# CM5_Schem_V2.net
KiCad netlist of a schematic drawn in Altium Designer
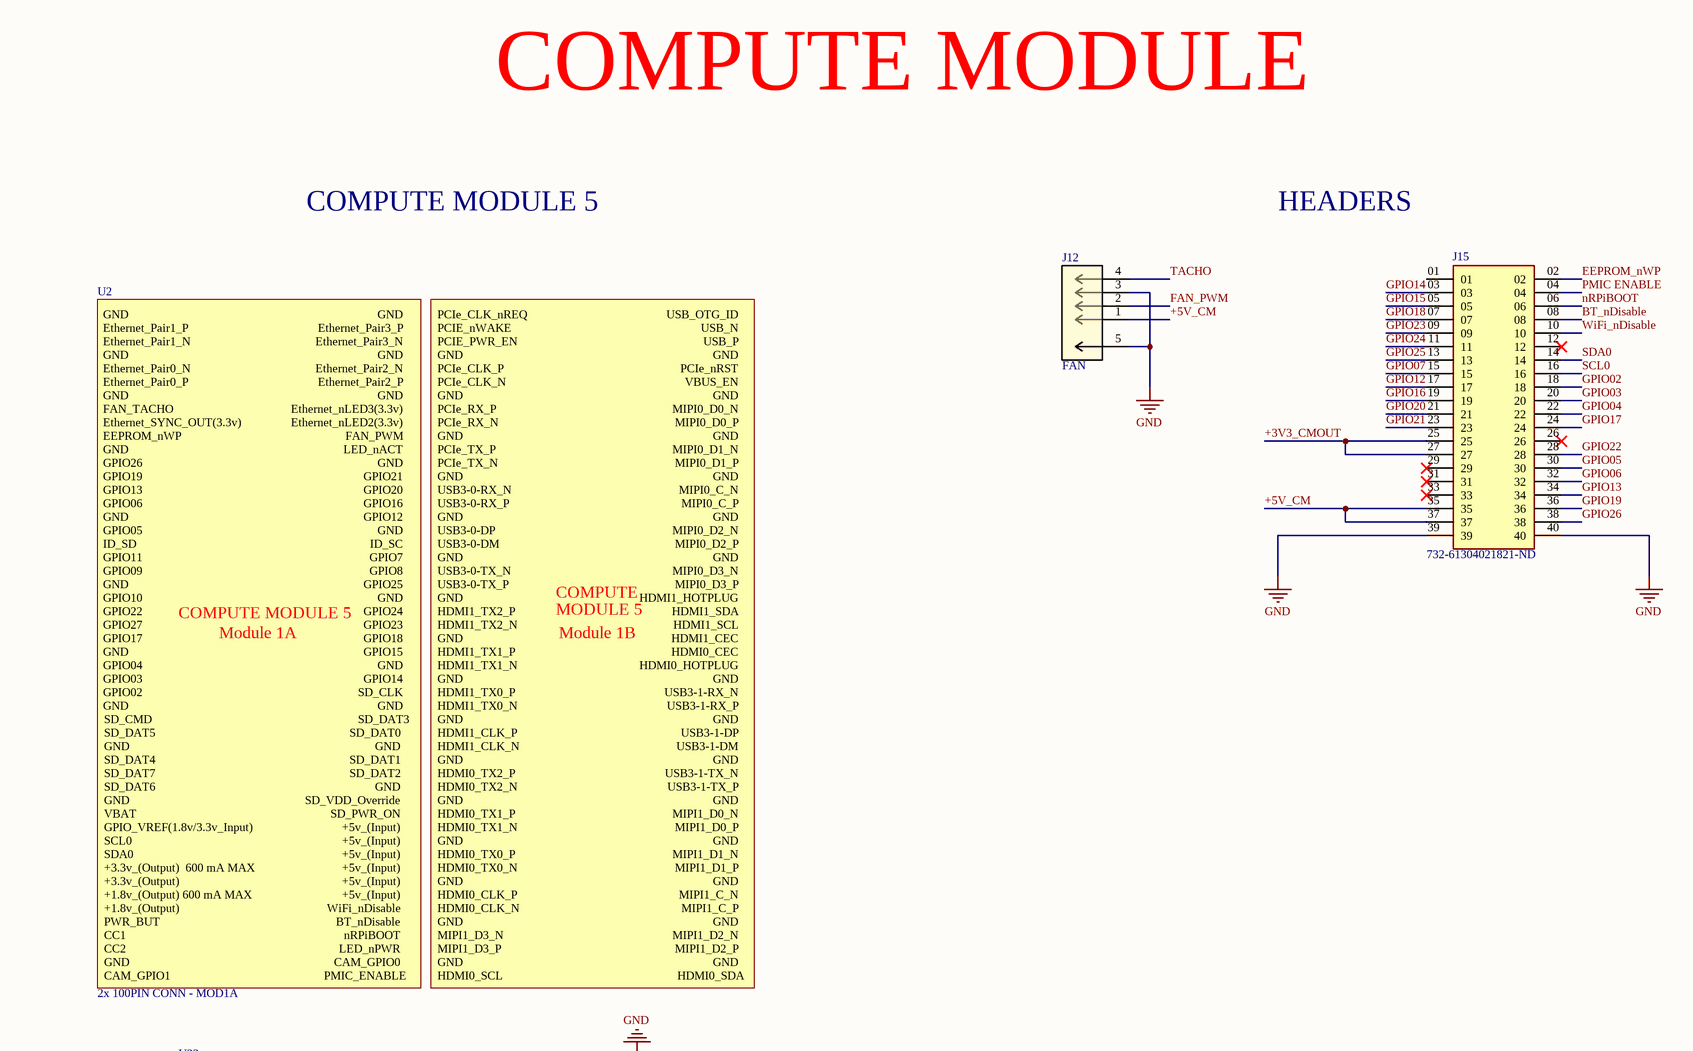
[diagram p0: CM5_Schem_V2.SchDoc, top left]
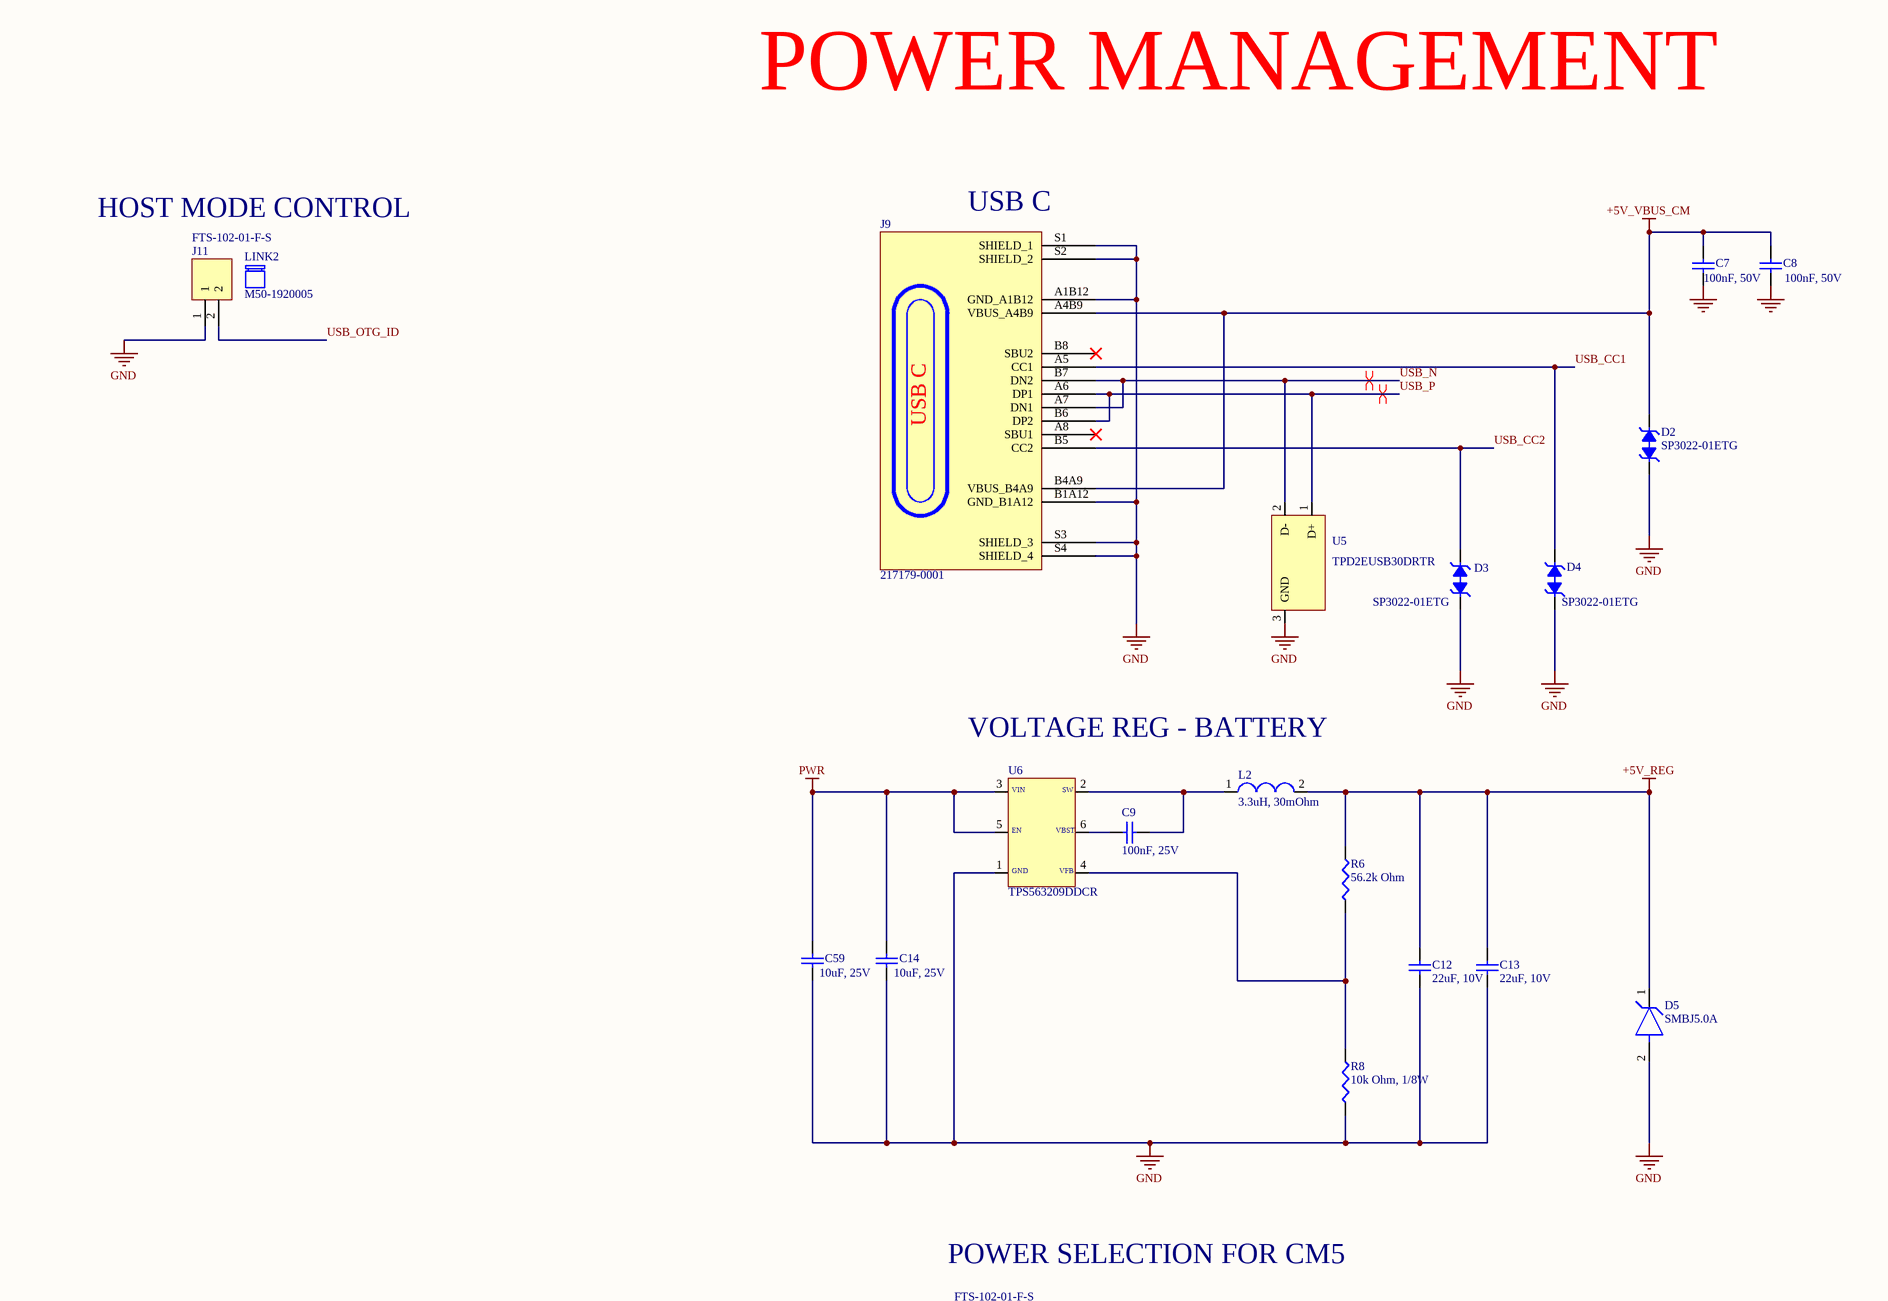
[diagram p1: CM5_Schem_V2.SchDoc, top right]
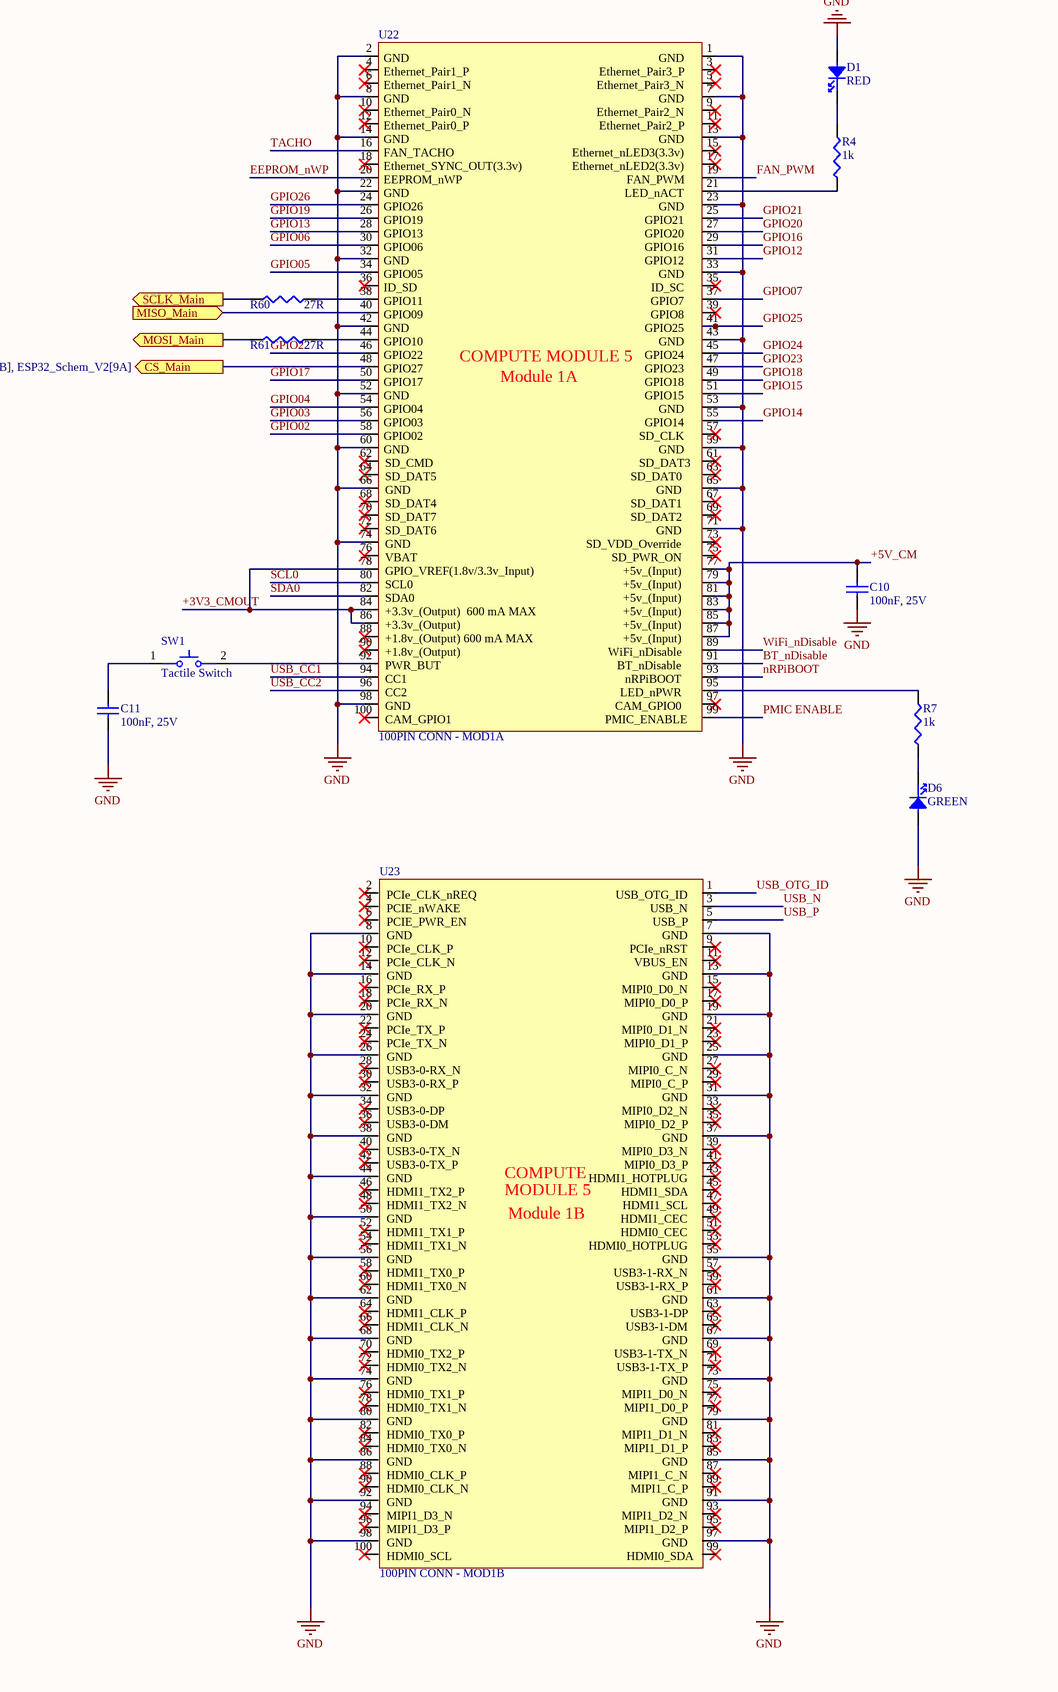
[diagram p2: CM5_Schem_V2.SchDoc, bottom left]
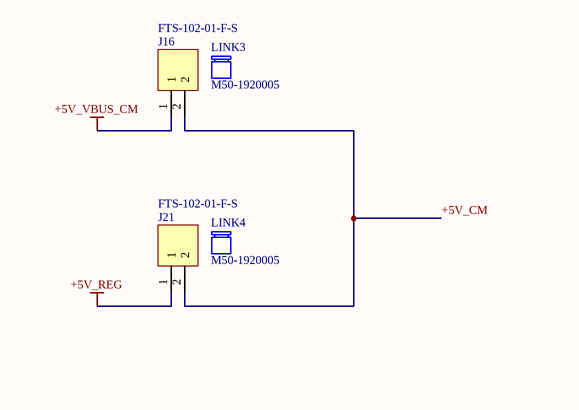
[diagram p3: CM5_Schem_V2.SchDoc, bottom right]

(export (version "E")
  (design (tool "Eeschema 10.0.6"))
  (components
    (comp (ref "C7")
      (value "100nF, 50V")
      (footprint "CAPC1005X55N")
      (fields
        (field (name "MANUFACTURER") "Samsung")
        (field (name "MANUFACTURER PART NUMBER") "CL05B104KB54PNC")
        (field (name "LCSC PART NUMBER") "C307331")
      )
      (libsource (lib "Schlib") (part "CL05B104KB54PNC"))
    )
    (comp (ref "C8")
      (value "100nF, 50V")
      (footprint "CAPC1005X55N")
      (fields
        (field (name "MANUFACTURER") "Samsung")
        (field (name "MANUFACTURER PART NUMBER") "CL05B104KB54PNC")
        (field (name "LCSC PART NUMBER") "C307331")
      )
      (libsource (lib "Schlib") (part "CL05B104KB54PNC"))
    )
    (comp (ref "C9")
      (value "100nF, 25V")
      (footprint "CAP_X7R_0805_AVX-M")
      (description "25V 100Nf X7R 10% 0805 Multilayer Ceramic Capacitors Mlcc Smd/Smt Rohs")
      (fields
        (field (name "MANUFACTURER") "Yageo Group")
        (field (name "MANUFACTURER PART NUMBER") "CC0805KRX7R8BB104")
      )
      (libsource (lib "Schlib_CM5+ESP32") (part "CC0805KRX7R8BB104"))
    )
    (comp (ref "C10")
      (value "100nF, 25V")
      (footprint "CAP_X7R_0805_AVX-M")
      (description "25V 100Nf X7R 10% 0805 Multilayer Ceramic Capacitors Mlcc Smd/Smt Rohs")
      (fields
        (field (name "MANUFACTURER") "Yageo Group")
        (field (name "MANUFACTURER PART NUMBER") "CC0805KRX7R8BB104")
      )
      (libsource (lib "Schlib_CM5+ESP32") (part "CC0805KRX7R8BB104"))
    )
    (comp (ref "C11")
      (value "100nF, 25V")
      (footprint "CAP_X7R_0805_AVX-M")
      (description "25V 100Nf X7R 10% 0805 Multilayer Ceramic Capacitors Mlcc Smd/Smt Rohs")
      (fields
        (field (name "MANUFACTURER") "Yageo Group")
        (field (name "MANUFACTURER PART NUMBER") "CC0805KRX7R8BB104")
      )
      (libsource (lib "Schlib_CM5+ESP32") (part "CC0805KRX7R8BB104"))
    )
    (comp (ref "C12")
      (value "22uF, 10V")
      (footprint "CAP_1608_TDK-M")
      (description "CAP CER 22UF 10V X5R 0603")
      (fields
        (field (name "MANUFACTURER") "TDK")
        (field (name "MANUFACTURER PART NUMBER") "C1608X5R1A226M080AC")
      )
      (libsource (lib "Schlib_CM5+ESP32") (part "C1608X5R1A226M080AC"))
    )
    (comp (ref "C13")
      (value "22uF, 10V")
      (footprint "CAP_1608_TDK-M")
      (description "CAP CER 22UF 10V X5R 0603")
      (fields
        (field (name "MANUFACTURER") "TDK")
        (field (name "MANUFACTURER PART NUMBER") "C1608X5R1A226M080AC")
      )
      (libsource (lib "Schlib_CM5+ESP32") (part "C1608X5R1A226M080AC"))
    )
    (comp (ref "C14")
      (value "10uF, 25V")
      (footprint "CAPC2012X95N")
      (description "CAP CER 10UF 25V X5R 0805")
      (fields
        (field (name "MANUFACTURER") "TAIYO YUDEN")
        (field (name "MANUFACTURER PART NUMBER") "TMK212BBJ106KG-T")
      )
      (libsource (lib "Schlib_CM5+ESP32") (part "TMK212BBJ106KG-T"))
    )
    (comp (ref "C59")
      (value "10uF, 25V")
      (footprint "CAPC2012X95N")
      (description "CAP CER 10UF 25V X5R 0805")
      (fields
        (field (name "MANUFACTURER") "TAIYO YUDEN")
        (field (name "MANUFACTURER PART NUMBER") "TMK212BBJ106KG-T")
      )
      (libsource (lib "Schlib_CM5+ESP32") (part "TMK212BBJ106KG-T"))
    )
    (comp (ref "D1")
      (value "RED")
      (footprint "LED0402R")
      (description "Single Color LED, Super Red, 0.5mm")
      (fields
        (field (name "MANUFACTURER") "Vishay")
        (field (name "MANUFACTURER PART NUMBER") "VLMS1500-GS08")
      )
      (libsource (lib "Schlib_PersonalProject") (part "VLMS1500-GS08"))
    )
    (comp (ref "D2")
      (value "SP3022-01ETG")
      (footprint "SOD882")
      (description "TVS DIODE 5.3VWM 12VC SOD882")
      (fields (field (name "MANUFACTURER") "Littelfuse") (field (name "LCSC PART NUMBER") "C126840"))
      (libsource (lib "Schlib_CM5+ESP32") (part "SP3022-01ETG"))
    )
    (comp (ref "D3")
      (value "SP3022-01ETG")
      (footprint "SOD882")
      (description "TVS DIODE 5.3VWM 12VC SOD882")
      (fields (field (name "MANUFACTURER") "Littelfuse") (field (name "LCSC PART NUMBER") "C126840"))
      (libsource (lib "Schlib_CM5+ESP32") (part "SP3022-01ETG"))
    )
    (comp (ref "D4")
      (value "SP3022-01ETG")
      (footprint "SOD882")
      (description "TVS DIODE 5.3VWM 12VC SOD882")
      (fields (field (name "MANUFACTURER") "Littelfuse") (field (name "LCSC PART NUMBER") "C126840"))
      (libsource (lib "Schlib_CM5+ESP32") (part "SP3022-01ETG"))
    )
    (comp (ref "D5")
      (value "SMBJ5.0A")
      (footprint "DO-214AASMB_J-BEND_LTF-M")
      (description "TVS DIODE 5VWM 9.2VC DO214AA")
      (fields (field (name "MANUFACTURER") "Littelfuse") (field (name "LCSC PART NUMBER") "C83333"))
      (libsource (lib "Schlib_CM5+ESP32") (part "SMBJ5.0A"))
    )
    (comp (ref "D6")
      (value "GREEN")
      (footprint "LED0402G")
      (description "Single Color LED, Yellow Green, 0.5mm")
      (fields
        (field (name "MANUFACTURER") "Vishay")
        (field (name "MANUFACTURER PART NUMBER") "VLMG1500-GS08")
      )
      (libsource (lib "Schlib_PersonalProject") (part "VLMG1500-GS08"))
    )
    (comp (ref "J9")
      (value "217179-0001")
      (footprint "FP-2171790001-MFG")
      (description "USB Connector, 16 Contact(s), Female, Right Angle, Surface Mount Terminal, Locking, Receptacle")
      (fields (field (name "MANUFACTURER") "Molex") (field (name "LCSC PART NUMBER") "C3197684"))
      (libsource (lib "Schlib_PersonalProject") (part "217179-0001"))
    )
    (comp (ref "J11")
      (value "FTS-102-01-F-S")
      (footprint "HDR_1x2_1.27MM")
      (description "Board Connector, 2 Contact(s), 1 Row(s), Male, Straight, Solder Terminal")
      (fields (field (name "MANUFACTURER") "Samtec") (field (name "LCSC PART NUMBER") "C6045317"))
      (libsource (lib "Schlib_PersonalProject") (part "FTS-102-01-F-S"))
    )
    (comp (ref "J12")
      (value "FAN")
      (footprint "CONN4_BM04B-SRSS_JST")
      (description "CONN HEADER SMD 4POS 1MM")
      (fields (field (name "MANUFACTURER") "JST") (field (name "MANUFACTURER PART NUMBER") "BM04B-SRSS-TB"))
      (libsource (lib "Schlib_CM5+ESP32") (part "BM04B-SRSS-TB"))
    )
    (comp (ref "J15")
      (value "732-61304021821-ND")
      (footprint "SAMTEC_MTSW-120-X-X-D-X")
      (description "Pin Header, Board-to-Board, 2.54 mm, 2 Rows, 40 Contacts, Through Hole, MTSW Series")
      (fields
        (field (name "MANUFACTURER") "Samtec")
        (field (name "MANUFACTURER PART NUMBER") "MTSW-120-22-T-D-380")
      )
      (libsource (lib "Schlib_CM5+ESP32") (part "MTSW-120-22-T-D-380"))
    )
    (comp (ref "J16")
      (value "FTS-102-01-F-S")
      (footprint "HDR_1x2_1.27MM")
      (description "Board Connector, 2 Contact(s), 1 Row(s), Male, Straight, Solder Terminal")
      (fields (field (name "MANUFACTURER") "Samtec") (field (name "LCSC PART NUMBER") "C6045317"))
      (libsource (lib "Schlib_PersonalProject") (part "FTS-102-01-F-S"))
    )
    (comp (ref "J21")
      (value "FTS-102-01-F-S")
      (footprint "HDR_1x2_1.27MM")
      (description "Board Connector, 2 Contact(s), 1 Row(s), Male, Straight, Solder Terminal")
      (fields (field (name "MANUFACTURER") "Samtec") (field (name "LCSC PART NUMBER") "C6045317"))
      (libsource (lib "Schlib_PersonalProject") (part "FTS-102-01-F-S"))
    )
    (comp (ref "L2")
      (value "3.3uH, 30mOhm")
      (footprint "IND_VLS6045EX-3R3N")
      (description "FIXED IND 3.3UH 4.95A 30MOHM SMD")
      (fields (field (name "MANUFACTURER") "TDK") (field (name "MANUFACTURER PART NUMBER") "VLS6045EX-3R3N"))
      (libsource (lib "Schlib_CM5+ESP32") (part "VLS6045EX-3R3N"))
    )
    (comp (ref "LINK2")
      (value "M50-1920005")
      (description "Interconnection Device")
      (fields (field (name "MANUFACTURER") "Harwin") (field (name "LCSC PART NUMBER") "C6985646"))
      (libsource (lib "Schlib_PersonalProject") (part "M50-1920005"))
    )
    (comp (ref "LINK3")
      (value "M50-1920005")
      (description "Interconnection Device")
      (fields (field (name "MANUFACTURER") "Harwin") (field (name "LCSC PART NUMBER") "C6985646"))
      (libsource (lib "Schlib_PersonalProject") (part "M50-1920005"))
    )
    (comp (ref "LINK4")
      (value "M50-1920005")
      (description "Interconnection Device")
      (fields (field (name "MANUFACTURER") "Harwin") (field (name "LCSC PART NUMBER") "C6985646"))
      (libsource (lib "Schlib_PersonalProject") (part "M50-1920005"))
    )
    (comp (ref "R4")
      (value "1k")
      (footprint "RESC1005X40N")
      (description "RES 1K OHM 1% 1/16W 0402")
      (fields
        (field (name "MANUFACTURER") "Yageo")
        (field (name "MANUFACTURER PART NUMBER") "RC0402FR-071KL")
      )
      (libsource (lib "Schlib_CM5+ESP32") (part "RC0402FR-071KL"))
    )
    (comp (ref "R6")
      (value "56.2k Ohm")
      (footprint "RESC0603X26N")
      (description "RES 56.2K OHM 1% 1/20W 0201")
      (fields
        (field (name "MANUFACTURER") "Yageo")
        (field (name "MANUFACTURER PART NUMBER") "RC0201FR-0756K2L")
      )
      (libsource (lib "Schlib_CM5+ESP32") (part "RC0201FR-0756K2L"))
    )
    (comp (ref "R7")
      (value "1k")
      (footprint "RESC1005X40N")
      (description "RES 1K OHM 1% 1/16W 0402")
      (fields
        (field (name "MANUFACTURER") "Yageo")
        (field (name "MANUFACTURER PART NUMBER") "RC0402FR-071KL")
      )
      (libsource (lib "Schlib_CM5+ESP32") (part "RC0402FR-071KL"))
    )
    (comp (ref "R8")
      (value "10k Ohm, 1/8W")
      (footprint "RESC1005X40N")
      (description "RES 10K OHM 1% 1/8W 0402")
      (fields
        (field (name "MANUFACTURER") "Yageo Group")
        (field (name "MANUFACTURER PART NUMBER") "RC0402FR-7W10KL")
      )
      (libsource (lib "Schlib_CM5+ESP32") (part "RC0402FR-7W10KL"))
    )
    (comp (ref "R60")
      (value "27R")
      (footprint "RESC1005X37N")
      (fields
        (field (name "MANUFACTURER") "Yageo")
        (field (name "MANUFACTURER PART NUMBER") "RC0402FR-0727RL")
        (field (name "TOLERANCE") "1%")
      )
      (libsource (lib "Schlib") (part "RC0402FR-0727RL"))
    )
    (comp (ref "R61")
      (value "27R")
      (footprint "RESC1005X37N")
      (fields
        (field (name "MANUFACTURER") "Yageo")
        (field (name "MANUFACTURER PART NUMBER") "RC0402FR-0727RL")
        (field (name "TOLERANCE") "1%")
      )
      (libsource (lib "Schlib") (part "RC0402FR-0727RL"))
    )
    (comp (ref "SW1")
      (value "Tactile Switch")
      (footprint "SWITCH_43SMTR92LFS")
      (description "SWITCH TACTILE SPST-NO 0.05A 12V")
      (fields
        (field (name "MANUFACTURER") "ITT C&K")
        (field (name "MANUFACTURER PART NUMBER") "PTS645SM43SMTR92LFS")
      )
      (libsource (lib "Schlib_CM5+ESP32") (part "PTS645SM43SMTR92LFS"))
    )
    (comp (ref "U2")
      (value "2x 100PIN CONN - MOD1A")
      (footprint "RPI CM5")
      (description "2x CONN RCPT 100POS SMD GOLD")
      (fields
        (field (name "MANUFACTURER") "Hirose")
        (field (name "MANUFACTURER PART NUMBER") "DF40C-100DS-0.4V(51)")
      )
      (libsource (lib "Schlib_CM5+ESP32") (part "CM5 Courtyard"))
    )
    (comp (ref "U5")
      (value "TPD2EUSB30DRTR")
      (footprint "SOTFL35P100X50-3N")
      (description "TVS DIODE 5.5VWM 8VC SOT3")
      (fields (field (name "MANUFACTURER") "Texas Instruments") (field (name "LCSC PART NUMBER") "C97502"))
      (libsource (lib "Schlib_CM5+ESP32") (part "TPD2EUSB30DRTR"))
    )
    (comp (ref "U6")
      (value "TPS563209DDCR")
      (footprint "DDC0006A")
      (description "IC REG BUCK ADJ 3A SOT23")
      (fields (field (name "MANUFACTURER") "Texas Instruments") (field (name "LCSC PART NUMBER") "C181974"))
      (libsource (lib "Schlib_CM5+ESP32") (part "TPS563209DDCR"))
    )
    (comp (ref "U22")
      (value "100PIN CONN - MOD1A")
      (footprint "HIROSE_DF40C-100DS-0.4V(51)")
      (description "CONN RCPT 100POS SMD GOLD")
      (fields
        (field (name "MANUFACTURER") "Hirose")
        (field (name "MANUFACTURER PART NUMBER") "DF40C-100DS-0.4V(51)")
      )
      (libsource (lib "Schlib_CM5+ESP32") (part "DF40C-100DS-0.4V(51)_MOD1A"))
    )
    (comp (ref "U23")
      (value "100PIN CONN - MOD1B")
      (footprint "HIROSE_DF40C-100DS-0.4V(51)")
      (description "CONN RCPT 100POS SMD GOLD")
      (fields
        (field (name "MANUFACTURER") "Hirose")
        (field (name "MANUFACTURER PART NUMBER") "DF40C-100DS-0.4V(51)")
      )
      (libsource (lib "Schlib_CM5+ESP32") (part "DF40C-100DS-0.4V(51)_MOD1B"))
    )
  )
  (nets
    (net (code "1") (name "+5V_REG") (class "Default")
      (node (ref "C12") (pin "1") (pinfunction "1_1") (pintype "passive"))
      (node (ref "C13") (pin "1") (pinfunction "1_1") (pintype "passive"))
      (node (ref "D5") (pin "1") (pinfunction "1_1") (pintype "passive"))
      (node (ref "J21") (pin "1") (pinfunction "1_1") (pintype "passive"))
      (node (ref "L2") (pin "2") (pinfunction "2_2") (pintype "passive"))
      (node (ref "R6") (pin "2") (pinfunction "2_2") (pintype "passive"))
    )
    (net (code "2") (name "+5V_VBUS_CM") (class "Default")
      (node (ref "C7") (pin "2") (pinfunction "2_2") (pintype "passive"))
      (node (ref "C8") (pin "2") (pinfunction "2_2") (pintype "passive"))
      (node (ref "D2") (pin "2") (pinfunction "2_2") (pintype "passive"))
      (node (ref "J16") (pin "1") (pinfunction "1_1") (pintype "passive"))
      (node (ref "J9") (pin "A4B9") (pinfunction "VBUS_A4B9_A4B9") (pintype "passive"))
      (node (ref "J9") (pin "B4A9") (pinfunction "VBUS_B4A9_B4A9") (pintype "passive"))
    )
    (net (code "3") (name "/+3V3_CMOUT") (class "Default")
      (node (ref "J15") (pin "25") (pinfunction "25_25") (pintype "passive"))
      (node (ref "J15") (pin "27") (pinfunction "27_27") (pintype "passive"))
      (node (ref "U22") (pin "78") (pinfunction "78_78") (pintype "passive"))
      (node (ref "U22") (pin "84") (pinfunction "84_84") (pintype "passive"))
      (node (ref "U22") (pin "86") (pinfunction "86_86") (pintype "passive"))
    )
    (net (code "4") (name "/+5V_CM") (class "Default")
      (node (ref "C10") (pin "2") (pinfunction "2_2") (pintype "passive"))
      (node (ref "J12") (pin "1") (pinfunction "1_1") (pintype "passive"))
      (node (ref "J15") (pin "35") (pinfunction "35_35") (pintype "passive"))
      (node (ref "J15") (pin "37") (pinfunction "37_37") (pintype "passive"))
      (node (ref "J16") (pin "2") (pinfunction "2_2") (pintype "passive"))
      (node (ref "J21") (pin "2") (pinfunction "2_2") (pintype "passive"))
      (node (ref "U22") (pin "77") (pinfunction "77_77") (pintype "passive"))
      (node (ref "U22") (pin "79") (pinfunction "79_79") (pintype "passive"))
      (node (ref "U22") (pin "81") (pinfunction "81_81") (pintype "passive"))
      (node (ref "U22") (pin "83") (pinfunction "83_83") (pintype "passive"))
      (node (ref "U22") (pin "85") (pinfunction "85_85") (pintype "passive"))
      (node (ref "U22") (pin "87") (pinfunction "87_87") (pintype "passive"))
    )
    (net (code "5") (name "/BT_nDisable") (class "Default")
      (node (ref "J15") (pin "08") (pinfunction "08_08") (pintype "passive"))
      (node (ref "U22") (pin "91") (pinfunction "91_91") (pintype "passive"))
    )
    (net (code "6") (name "/CS_Main") (class "Default")
      (node (ref "U22") (pin "48") (pinfunction "48_48") (pintype "passive"))
    )
    (net (code "7") (name "/EEPROM_nWP") (class "Default")
      (node (ref "J15") (pin "02") (pinfunction "02_02") (pintype "passive"))
      (node (ref "U22") (pin "20") (pinfunction "20_20") (pintype "passive"))
    )
    (net (code "8") (name "/FAN_PWM") (class "Default")
      (node (ref "J12") (pin "2") (pinfunction "2_2") (pintype "passive"))
      (node (ref "U22") (pin "19") (pinfunction "19_19") (pintype "passive"))
    )
    (net (code "9") (name "/GPIO02") (class "Default")
      (node (ref "J15") (pin "18") (pinfunction "18_18") (pintype "passive"))
      (node (ref "U22") (pin "58") (pinfunction "58_58") (pintype "passive"))
    )
    (net (code "10") (name "/GPIO03") (class "Default")
      (node (ref "J15") (pin "20") (pinfunction "20_20") (pintype "passive"))
      (node (ref "U22") (pin "56") (pinfunction "56_56") (pintype "passive"))
    )
    (net (code "11") (name "/GPIO04") (class "Default")
      (node (ref "J15") (pin "22") (pinfunction "22_22") (pintype "passive"))
      (node (ref "U22") (pin "54") (pinfunction "54_54") (pintype "passive"))
    )
    (net (code "12") (name "/GPIO05") (class "Default")
      (node (ref "J15") (pin "30") (pinfunction "30_30") (pintype "passive"))
      (node (ref "U22") (pin "34") (pinfunction "34_34") (pintype "passive"))
    )
    (net (code "13") (name "/GPIO06") (class "Default")
      (node (ref "J15") (pin "32") (pinfunction "32_32") (pintype "passive"))
      (node (ref "U22") (pin "30") (pinfunction "30_30") (pintype "passive"))
    )
    (net (code "14") (name "/GPIO07") (class "Default")
      (node (ref "J15") (pin "15") (pinfunction "15_15") (pintype "passive"))
      (node (ref "U22") (pin "37") (pinfunction "37_37") (pintype "passive"))
    )
    (net (code "15") (name "/GPIO12") (class "Default")
      (node (ref "J15") (pin "17") (pinfunction "17_17") (pintype "passive"))
      (node (ref "U22") (pin "31") (pinfunction "31_31") (pintype "passive"))
    )
    (net (code "16") (name "/GPIO13") (class "Default")
      (node (ref "J15") (pin "34") (pinfunction "34_34") (pintype "passive"))
      (node (ref "U22") (pin "28") (pinfunction "28_28") (pintype "passive"))
    )
    (net (code "17") (name "/GPIO14") (class "Default")
      (node (ref "J15") (pin "03") (pinfunction "03_03") (pintype "passive"))
      (node (ref "U22") (pin "55") (pinfunction "55_55") (pintype "passive"))
    )
    (net (code "18") (name "/GPIO15") (class "Default")
      (node (ref "J15") (pin "05") (pinfunction "05_05") (pintype "passive"))
      (node (ref "U22") (pin "51") (pinfunction "51_51") (pintype "passive"))
    )
    (net (code "19") (name "/GPIO16") (class "Default")
      (node (ref "J15") (pin "19") (pinfunction "19_19") (pintype "passive"))
      (node (ref "U22") (pin "29") (pinfunction "29_29") (pintype "passive"))
    )
    (net (code "20") (name "/GPIO17") (class "Default")
      (node (ref "J15") (pin "24") (pinfunction "24_24") (pintype "passive"))
      (node (ref "U22") (pin "50") (pinfunction "50_50") (pintype "passive"))
    )
    (net (code "21") (name "/GPIO18") (class "Default")
      (node (ref "J15") (pin "07") (pinfunction "07_07") (pintype "passive"))
      (node (ref "U22") (pin "49") (pinfunction "49_49") (pintype "passive"))
    )
    (net (code "22") (name "/GPIO19") (class "Default")
      (node (ref "J15") (pin "36") (pinfunction "36_36") (pintype "passive"))
      (node (ref "U22") (pin "26") (pinfunction "26_26") (pintype "passive"))
    )
    (net (code "23") (name "/GPIO20") (class "Default")
      (node (ref "J15") (pin "21") (pinfunction "21_21") (pintype "passive"))
      (node (ref "U22") (pin "27") (pinfunction "27_27") (pintype "passive"))
    )
    (net (code "24") (name "/GPIO21") (class "Default")
      (node (ref "J15") (pin "23") (pinfunction "23_23") (pintype "passive"))
      (node (ref "U22") (pin "25") (pinfunction "25_25") (pintype "passive"))
    )
    (net (code "25") (name "/GPIO22") (class "Default")
      (node (ref "J15") (pin "28") (pinfunction "28_28") (pintype "passive"))
      (node (ref "U22") (pin "46") (pinfunction "46_46") (pintype "passive"))
    )
    (net (code "26") (name "/GPIO23") (class "Default")
      (node (ref "J15") (pin "09") (pinfunction "09_09") (pintype "passive"))
      (node (ref "U22") (pin "47") (pinfunction "47_47") (pintype "passive"))
    )
    (net (code "27") (name "/GPIO24") (class "Default")
      (node (ref "J15") (pin "11") (pinfunction "11_11") (pintype "passive"))
      (node (ref "U22") (pin "45") (pinfunction "45_45") (pintype "passive"))
    )
    (net (code "28") (name "/GPIO25") (class "Default")
      (node (ref "J15") (pin "13") (pinfunction "13_13") (pintype "passive"))
      (node (ref "U22") (pin "41") (pinfunction "41_41") (pintype "passive"))
    )
    (net (code "29") (name "/GPIO26") (class "Default")
      (node (ref "J15") (pin "38") (pinfunction "38_38") (pintype "passive"))
      (node (ref "U22") (pin "24") (pinfunction "24_24") (pintype "passive"))
    )
    (net (code "30") (name "/MISO_Main") (class "Default")
      (node (ref "U22") (pin "40") (pinfunction "40_40") (pintype "passive"))
    )
    (net (code "31") (name "/MOSI_Main") (class "Default")
      (node (ref "R61") (pin "1") (pinfunction "1_1") (pintype "passive"))
    )
    (net (code "32") (name "/PMIC ENABLE") (class "Default")
      (node (ref "J15") (pin "04") (pinfunction "04_04") (pintype "passive"))
      (node (ref "U22") (pin "99") (pinfunction "99_99") (pintype "passive"))
    )
    (net (code "33") (name "/SCL0") (class "Default")
      (node (ref "J15") (pin "16") (pinfunction "16_16") (pintype "passive"))
      (node (ref "U22") (pin "80") (pinfunction "80_80") (pintype "passive"))
    )
    (net (code "34") (name "/SCLK_Main") (class "Default")
      (node (ref "R60") (pin "1") (pinfunction "1_1") (pintype "passive"))
    )
    (net (code "35") (name "/SDA0") (class "Default")
      (node (ref "J15") (pin "14") (pinfunction "14_14") (pintype "passive"))
      (node (ref "U22") (pin "82") (pinfunction "82_82") (pintype "passive"))
    )
    (net (code "36") (name "/TACHO") (class "Default")
      (node (ref "J12") (pin "4") (pinfunction "4_4") (pintype "passive"))
      (node (ref "U22") (pin "16") (pinfunction "16_16") (pintype "passive"))
    )
    (net (code "37") (name "/USB_CC1") (class "Default")
      (node (ref "D4") (pin "2") (pinfunction "2_2") (pintype "passive"))
      (node (ref "J9") (pin "A5") (pinfunction "CC1_A5") (pintype "passive"))
      (node (ref "U22") (pin "94") (pinfunction "94_94") (pintype "passive"))
    )
    (net (code "38") (name "/USB_CC2") (class "Default")
      (node (ref "D3") (pin "2") (pinfunction "2_2") (pintype "passive"))
      (node (ref "J9") (pin "B5") (pinfunction "CC2_B5") (pintype "passive"))
      (node (ref "U22") (pin "96") (pinfunction "96_96") (pintype "passive"))
    )
    (net (code "39") (name "/USB_N") (class "Default")
      (node (ref "J9") (pin "A7") (pinfunction "DN1_A7") (pintype "passive"))
      (node (ref "J9") (pin "B7") (pinfunction "DN2_B7") (pintype "passive"))
      (node (ref "U23") (pin "3") (pinfunction "3_3") (pintype "passive"))
      (node (ref "U5") (pin "2") (pinfunction "D-_2") (pintype "passive"))
    )
    (net (code "40") (name "/USB_OTG_ID") (class "Default")
      (node (ref "J11") (pin "2") (pinfunction "2_2") (pintype "passive"))
      (node (ref "U23") (pin "1") (pinfunction "1_1") (pintype "passive"))
    )
    (net (code "41") (name "/USB_P") (class "Default")
      (node (ref "J9") (pin "A6") (pinfunction "DP1_A6") (pintype "passive"))
      (node (ref "J9") (pin "B6") (pinfunction "DP2_B6") (pintype "passive"))
      (node (ref "U23") (pin "5") (pinfunction "5_5") (pintype "passive"))
      (node (ref "U5") (pin "1") (pinfunction "D+_1") (pintype "passive"))
    )
    (net (code "42") (name "/WiFi_nDisable") (class "Default")
      (node (ref "J15") (pin "10") (pinfunction "10_10") (pintype "passive"))
      (node (ref "U22") (pin "89") (pinfunction "89_89") (pintype "passive"))
    )
    (net (code "43") (name "/nRPiBOOT") (class "Default")
      (node (ref "J15") (pin "06") (pinfunction "06_06") (pintype "passive"))
      (node (ref "U22") (pin "93") (pinfunction "93_93") (pintype "passive"))
    )
    (net (code "44") (name "GND") (class "Default")
      (node (ref "C10") (pin "1") (pinfunction "1_1") (pintype "passive"))
      (node (ref "C11") (pin "1") (pinfunction "1_1") (pintype "passive"))
      (node (ref "C12") (pin "2") (pinfunction "2_2") (pintype "passive"))
      (node (ref "C13") (pin "2") (pinfunction "2_2") (pintype "passive"))
      (node (ref "C14") (pin "1") (pinfunction "1_1") (pintype "passive"))
      (node (ref "C59") (pin "1") (pinfunction "1_1") (pintype "passive"))
      (node (ref "C7") (pin "1") (pinfunction "1_1") (pintype "passive"))
      (node (ref "C8") (pin "1") (pinfunction "1_1") (pintype "passive"))
      (node (ref "D1") (pin "2") (pinfunction "2_2") (pintype "passive"))
      (node (ref "D2") (pin "1") (pinfunction "1_1") (pintype "passive"))
      (node (ref "D3") (pin "1") (pinfunction "1_1") (pintype "passive"))
      (node (ref "D4") (pin "1") (pinfunction "1_1") (pintype "passive"))
      (node (ref "D5") (pin "2") (pinfunction "2_2") (pintype "passive"))
      (node (ref "D6") (pin "2") (pinfunction "2_2") (pintype "passive"))
      (node (ref "J11") (pin "1") (pinfunction "1_1") (pintype "passive"))
      (node (ref "J12") (pin "3") (pinfunction "3_3") (pintype "passive"))
      (node (ref "J12") (pin "5") (pinfunction "5_5") (pintype "passive"))
      (node (ref "J15") (pin "39") (pinfunction "39_39") (pintype "passive"))
      (node (ref "J15") (pin "40") (pinfunction "40_40") (pintype "passive"))
      (node (ref "J9") (pin "A1B12") (pinfunction "GND_A1B12_A1B12") (pintype "passive"))
      (node (ref "J9") (pin "B1A12") (pinfunction "GND_B1A12_B1A12") (pintype "passive"))
      (node (ref "J9") (pin "S1") (pinfunction "SHIELD_1_S1") (pintype "passive"))
      (node (ref "J9") (pin "S2") (pinfunction "SHIELD_2_S2") (pintype "passive"))
      (node (ref "J9") (pin "S3") (pinfunction "SHIELD_3_S3") (pintype "passive"))
      (node (ref "J9") (pin "S4") (pinfunction "SHIELD_4_S4") (pintype "passive"))
      (node (ref "R8") (pin "1") (pinfunction "1_1") (pintype "passive"))
      (node (ref "U22") (pin "1") (pinfunction "1_1") (pintype "passive"))
      (node (ref "U22") (pin "13") (pinfunction "13_13") (pintype "passive"))
      (node (ref "U22") (pin "14") (pinfunction "14_14") (pintype "passive"))
      (node (ref "U22") (pin "2") (pinfunction "2_2") (pintype "passive"))
      (node (ref "U22") (pin "22") (pinfunction "22_22") (pintype "passive"))
      (node (ref "U22") (pin "23") (pinfunction "23_23") (pintype "passive"))
      (node (ref "U22") (pin "32") (pinfunction "32_32") (pintype "passive"))
      (node (ref "U22") (pin "33") (pinfunction "33_33") (pintype "passive"))
      (node (ref "U22") (pin "42") (pinfunction "42_42") (pintype "passive"))
      (node (ref "U22") (pin "43") (pinfunction "43_43") (pintype "passive"))
      (node (ref "U22") (pin "52") (pinfunction "52_52") (pintype "passive"))
      (node (ref "U22") (pin "53") (pinfunction "53_53") (pintype "passive"))
      (node (ref "U22") (pin "59") (pinfunction "59_59") (pintype "passive"))
      (node (ref "U22") (pin "60") (pinfunction "60_60") (pintype "passive"))
      (node (ref "U22") (pin "65") (pinfunction "65_65") (pintype "passive"))
      (node (ref "U22") (pin "66") (pinfunction "66_66") (pintype "passive"))
      (node (ref "U22") (pin "7") (pinfunction "7_7") (pintype "passive"))
      (node (ref "U22") (pin "71") (pinfunction "71_71") (pintype "passive"))
      (node (ref "U22") (pin "74") (pinfunction "74_74") (pintype "passive"))
      (node (ref "U22") (pin "8") (pinfunction "8_8") (pintype "passive"))
      (node (ref "U22") (pin "98") (pinfunction "98_98") (pintype "passive"))
      (node (ref "U23") (pin "13") (pinfunction "13_13") (pintype "passive"))
      (node (ref "U23") (pin "14") (pinfunction "14_14") (pintype "passive"))
      (node (ref "U23") (pin "19") (pinfunction "19_19") (pintype "passive"))
      (node (ref "U23") (pin "20") (pinfunction "20_20") (pintype "passive"))
      (node (ref "U23") (pin "25") (pinfunction "25_25") (pintype "passive"))
      (node (ref "U23") (pin "26") (pinfunction "26_26") (pintype "passive"))
      (node (ref "U23") (pin "31") (pinfunction "31_31") (pintype "passive"))
      (node (ref "U23") (pin "32") (pinfunction "32_32") (pintype "passive"))
      (node (ref "U23") (pin "37") (pinfunction "37_37") (pintype "passive"))
      (node (ref "U23") (pin "38") (pinfunction "38_38") (pintype "passive"))
      (node (ref "U23") (pin "44") (pinfunction "44_44") (pintype "passive"))
      (node (ref "U23") (pin "50") (pinfunction "50_50") (pintype "passive"))
      (node (ref "U23") (pin "55") (pinfunction "55_55") (pintype "passive"))
      (node (ref "U23") (pin "56") (pinfunction "56_56") (pintype "passive"))
      (node (ref "U23") (pin "61") (pinfunction "61_61") (pintype "passive"))
      (node (ref "U23") (pin "62") (pinfunction "62_62") (pintype "passive"))
      (node (ref "U23") (pin "67") (pinfunction "67_67") (pintype "passive"))
      (node (ref "U23") (pin "68") (pinfunction "68_68") (pintype "passive"))
      (node (ref "U23") (pin "7") (pinfunction "7_7") (pintype "passive"))
      (node (ref "U23") (pin "73") (pinfunction "73_73") (pintype "passive"))
      (node (ref "U23") (pin "74") (pinfunction "74_74") (pintype "passive"))
      (node (ref "U23") (pin "79") (pinfunction "79_79") (pintype "passive"))
      (node (ref "U23") (pin "8") (pinfunction "8_8") (pintype "passive"))
      (node (ref "U23") (pin "80") (pinfunction "80_80") (pintype "passive"))
      (node (ref "U23") (pin "85") (pinfunction "85_85") (pintype "passive"))
      (node (ref "U23") (pin "86") (pinfunction "86_86") (pintype "passive"))
      (node (ref "U23") (pin "91") (pinfunction "91_91") (pintype "passive"))
      (node (ref "U23") (pin "92") (pinfunction "92_92") (pintype "passive"))
      (node (ref "U23") (pin "97") (pinfunction "97_97") (pintype "passive"))
      (node (ref "U23") (pin "98") (pinfunction "98_98") (pintype "passive"))
      (node (ref "U5") (pin "3") (pinfunction "GND_3") (pintype "passive"))
      (node (ref "U6") (pin "1") (pinfunction "1_1") (pintype "passive"))
    )
    (net (code "45") (name "Net-(C9-Pad1)") (class "Default")
      (node (ref "C9") (pin "1") (pinfunction "1_1") (pintype "passive"))
      (node (ref "U6") (pin "6") (pinfunction "6_6") (pintype "passive"))
    )
    (net (code "46") (name "Net-(C9-Pad2)") (class "Default")
      (node (ref "C9") (pin "2") (pinfunction "2_2") (pintype "passive"))
      (node (ref "L2") (pin "1") (pinfunction "1_1") (pintype "passive"))
      (node (ref "U6") (pin "2") (pinfunction "2_2") (pintype "passive"))
    )
    (net (code "47") (name "Net-(C11-Pad2)") (class "Default")
      (node (ref "C11") (pin "2") (pinfunction "2_2") (pintype "passive"))
      (node (ref "SW1") (pin "1") (pinfunction "1_1") (pintype "passive"))
    )
    (net (code "48") (name "Net-(D1-Pad1)") (class "Default")
      (node (ref "D1") (pin "1") (pinfunction "1_1") (pintype "passive"))
      (node (ref "R4") (pin "2") (pinfunction "2_2") (pintype "passive"))
    )
    (net (code "49") (name "Net-(D6-Pad1)") (class "Default")
      (node (ref "D6") (pin "1") (pinfunction "1_1") (pintype "passive"))
      (node (ref "R7") (pin "1") (pinfunction "1_1") (pintype "passive"))
    )
    (net (code "50") (name "Net-(R4-Pad1)") (class "Default")
      (node (ref "R4") (pin "1") (pinfunction "1_1") (pintype "passive"))
      (node (ref "U22") (pin "21") (pinfunction "21_21") (pintype "passive"))
    )
    (net (code "51") (name "Net-(R6-Pad1)") (class "Default")
      (node (ref "R6") (pin "1") (pinfunction "1_1") (pintype "passive"))
      (node (ref "R8") (pin "2") (pinfunction "2_2") (pintype "passive"))
      (node (ref "U6") (pin "4") (pinfunction "4_4") (pintype "passive"))
    )
    (net (code "52") (name "Net-(R7-Pad2)") (class "Default")
      (node (ref "R7") (pin "2") (pinfunction "2_2") (pintype "passive"))
      (node (ref "U22") (pin "95") (pinfunction "95_95") (pintype "passive"))
    )
    (net (code "53") (name "Net-(R60-Pad2)") (class "Default")
      (node (ref "R60") (pin "2") (pinfunction "2_2") (pintype "passive"))
      (node (ref "U22") (pin "38") (pinfunction "38_38") (pintype "passive"))
    )
    (net (code "54") (name "Net-(R61-Pad2)") (class "Default")
      (node (ref "R61") (pin "2") (pinfunction "2_2") (pintype "passive"))
      (node (ref "U22") (pin "44") (pinfunction "44_44") (pintype "passive"))
    )
    (net (code "55") (name "Net-(SW1-Pad2)") (class "Default")
      (node (ref "SW1") (pin "2") (pinfunction "2_2") (pintype "passive"))
      (node (ref "U22") (pin "92") (pinfunction "92_92") (pintype "passive"))
    )
    (net (code "56") (name "PWR") (class "Default")
      (node (ref "C14") (pin "2") (pinfunction "2_2") (pintype "passive"))
      (node (ref "C59") (pin "2") (pinfunction "2_2") (pintype "passive"))
      (node (ref "U6") (pin "3") (pinfunction "3_3") (pintype "passive"))
      (node (ref "U6") (pin "5") (pinfunction "5_5") (pintype "passive"))
    )
    (net (code "57") (name "unconnected-(J9-SBU1-PadA8)") (class "Default")
      (node (ref "J9") (pin "A8") (pinfunction "SBU1_A8") (pintype "passive+no_connect"))
    )
    (net (code "58") (name "unconnected-(J9-SBU2-PadB8)") (class "Default")
      (node (ref "J9") (pin "B8") (pinfunction "SBU2_B8") (pintype "passive+no_connect"))
    )
    (net (code "59") (name "unconnected-(J15-Pad01)") (class "Default")
      (node (ref "J15") (pin "01") (pinfunction "01_01") (pintype "passive"))
    )
    (net (code "60") (name "unconnected-(J15-Pad12)") (class "Default")
      (node (ref "J15") (pin "12") (pinfunction "12_12") (pintype "passive+no_connect"))
    )
    (net (code "61") (name "unconnected-(J15-Pad26)") (class "Default")
      (node (ref "J15") (pin "26") (pinfunction "26_26") (pintype "passive+no_connect"))
    )
    (net (code "62") (name "unconnected-(J15-Pad29)") (class "Default")
      (node (ref "J15") (pin "29") (pinfunction "29_29") (pintype "passive+no_connect"))
    )
    (net (code "63") (name "unconnected-(J15-Pad31)") (class "Default")
      (node (ref "J15") (pin "31") (pinfunction "31_31") (pintype "passive+no_connect"))
    )
    (net (code "64") (name "unconnected-(J15-Pad33)") (class "Default")
      (node (ref "J15") (pin "33") (pinfunction "33_33") (pintype "passive+no_connect"))
    )
    (net (code "65") (name "unconnected-(U22-Pad3)") (class "Default")
      (node (ref "U22") (pin "3") (pinfunction "3_3") (pintype "passive+no_connect"))
    )
    (net (code "66") (name "unconnected-(U22-Pad4)") (class "Default")
      (node (ref "U22") (pin "4") (pinfunction "4_4") (pintype "passive+no_connect"))
    )
    (net (code "67") (name "unconnected-(U22-Pad5)") (class "Default")
      (node (ref "U22") (pin "5") (pinfunction "5_5") (pintype "passive+no_connect"))
    )
    (net (code "68") (name "unconnected-(U22-Pad6)") (class "Default")
      (node (ref "U22") (pin "6") (pinfunction "6_6") (pintype "passive+no_connect"))
    )
    (net (code "69") (name "unconnected-(U22-Pad9)") (class "Default")
      (node (ref "U22") (pin "9") (pinfunction "9_9") (pintype "passive+no_connect"))
    )
    (net (code "70") (name "unconnected-(U22-Pad10)") (class "Default")
      (node (ref "U22") (pin "10") (pinfunction "10_10") (pintype "passive+no_connect"))
    )
    (net (code "71") (name "unconnected-(U22-Pad11)") (class "Default")
      (node (ref "U22") (pin "11") (pinfunction "11_11") (pintype "passive+no_connect"))
    )
    (net (code "72") (name "unconnected-(U22-Pad12)") (class "Default")
      (node (ref "U22") (pin "12") (pinfunction "12_12") (pintype "passive+no_connect"))
    )
    (net (code "73") (name "unconnected-(U22-Pad15)") (class "Default")
      (node (ref "U22") (pin "15") (pinfunction "15_15") (pintype "passive+no_connect"))
    )
    (net (code "74") (name "unconnected-(U22-Pad17)") (class "Default")
      (node (ref "U22") (pin "17") (pinfunction "17_17") (pintype "passive+no_connect"))
    )
    (net (code "75") (name "unconnected-(U22-Pad18)") (class "Default")
      (node (ref "U22") (pin "18") (pinfunction "18_18") (pintype "passive+no_connect"))
    )
    (net (code "76") (name "unconnected-(U22-Pad35)") (class "Default")
      (node (ref "U22") (pin "35") (pinfunction "35_35") (pintype "passive+no_connect"))
    )
    (net (code "77") (name "unconnected-(U22-Pad36)") (class "Default")
      (node (ref "U22") (pin "36") (pinfunction "36_36") (pintype "passive+no_connect"))
    )
    (net (code "78") (name "unconnected-(U22-Pad39)") (class "Default")
      (node (ref "U22") (pin "39") (pinfunction "39_39") (pintype "passive+no_connect"))
    )
    (net (code "79") (name "unconnected-(U22-Pad57)") (class "Default")
      (node (ref "U22") (pin "57") (pinfunction "57_57") (pintype "passive+no_connect"))
    )
    (net (code "80") (name "unconnected-(U22-Pad61)") (class "Default")
      (node (ref "U22") (pin "61") (pinfunction "61_61") (pintype "passive+no_connect"))
    )
    (net (code "81") (name "unconnected-(U22-Pad62)") (class "Default")
      (node (ref "U22") (pin "62") (pinfunction "62_62") (pintype "passive+no_connect"))
    )
    (net (code "82") (name "unconnected-(U22-Pad63)") (class "Default")
      (node (ref "U22") (pin "63") (pinfunction "63_63") (pintype "passive+no_connect"))
    )
    (net (code "83") (name "unconnected-(U22-Pad64)") (class "Default")
      (node (ref "U22") (pin "64") (pinfunction "64_64") (pintype "passive+no_connect"))
    )
    (net (code "84") (name "unconnected-(U22-Pad67)") (class "Default")
      (node (ref "U22") (pin "67") (pinfunction "67_67") (pintype "passive+no_connect"))
    )
    (net (code "85") (name "unconnected-(U22-Pad68)") (class "Default")
      (node (ref "U22") (pin "68") (pinfunction "68_68") (pintype "passive+no_connect"))
    )
    (net (code "86") (name "unconnected-(U22-Pad69)") (class "Default")
      (node (ref "U22") (pin "69") (pinfunction "69_69") (pintype "passive+no_connect"))
    )
    (net (code "87") (name "unconnected-(U22-Pad70)") (class "Default")
      (node (ref "U22") (pin "70") (pinfunction "70_70") (pintype "passive+no_connect"))
    )
    (net (code "88") (name "unconnected-(U22-Pad72)") (class "Default")
      (node (ref "U22") (pin "72") (pinfunction "72_72") (pintype "passive+no_connect"))
    )
    (net (code "89") (name "unconnected-(U22-Pad73)") (class "Default")
      (node (ref "U22") (pin "73") (pinfunction "73_73") (pintype "passive+no_connect"))
    )
    (net (code "90") (name "unconnected-(U22-Pad75)") (class "Default")
      (node (ref "U22") (pin "75") (pinfunction "75_75") (pintype "passive+no_connect"))
    )
    (net (code "91") (name "unconnected-(U22-Pad76)") (class "Default")
      (node (ref "U22") (pin "76") (pinfunction "76_76") (pintype "passive+no_connect"))
    )
    (net (code "92") (name "unconnected-(U22-Pad88)") (class "Default")
      (node (ref "U22") (pin "88") (pinfunction "88_88") (pintype "passive+no_connect"))
    )
    (net (code "93") (name "unconnected-(U22-Pad90)") (class "Default")
      (node (ref "U22") (pin "90") (pinfunction "90_90") (pintype "passive+no_connect"))
    )
    (net (code "94") (name "unconnected-(U22-Pad97)") (class "Default")
      (node (ref "U22") (pin "97") (pinfunction "97_97") (pintype "passive+no_connect"))
    )
    (net (code "95") (name "unconnected-(U22-Pad100)") (class "Default")
      (node (ref "U22") (pin "100") (pinfunction "100_100") (pintype "passive+no_connect"))
    )
    (net (code "96") (name "unconnected-(U23-Pad2)") (class "Default")
      (node (ref "U23") (pin "2") (pinfunction "2_2") (pintype "passive+no_connect"))
    )
    (net (code "97") (name "unconnected-(U23-Pad4)") (class "Default")
      (node (ref "U23") (pin "4") (pinfunction "4_4") (pintype "passive+no_connect"))
    )
    (net (code "98") (name "unconnected-(U23-Pad6)") (class "Default")
      (node (ref "U23") (pin "6") (pinfunction "6_6") (pintype "passive+no_connect"))
    )
    (net (code "99") (name "unconnected-(U23-Pad9)") (class "Default")
      (node (ref "U23") (pin "9") (pinfunction "9_9") (pintype "passive+no_connect"))
    )
    (net (code "100") (name "unconnected-(U23-Pad10)") (class "Default")
      (node (ref "U23") (pin "10") (pinfunction "10_10") (pintype "passive+no_connect"))
    )
    (net (code "101") (name "unconnected-(U23-Pad11)") (class "Default")
      (node (ref "U23") (pin "11") (pinfunction "11_11") (pintype "passive+no_connect"))
    )
    (net (code "102") (name "unconnected-(U23-Pad12)") (class "Default")
      (node (ref "U23") (pin "12") (pinfunction "12_12") (pintype "passive+no_connect"))
    )
    (net (code "103") (name "unconnected-(U23-Pad15)") (class "Default")
      (node (ref "U23") (pin "15") (pinfunction "15_15") (pintype "passive+no_connect"))
    )
    (net (code "104") (name "unconnected-(U23-Pad16)") (class "Default")
      (node (ref "U23") (pin "16") (pinfunction "16_16") (pintype "passive+no_connect"))
    )
    (net (code "105") (name "unconnected-(U23-Pad17)") (class "Default")
      (node (ref "U23") (pin "17") (pinfunction "17_17") (pintype "passive+no_connect"))
    )
    (net (code "106") (name "unconnected-(U23-Pad18)") (class "Default")
      (node (ref "U23") (pin "18") (pinfunction "18_18") (pintype "passive+no_connect"))
    )
    (net (code "107") (name "unconnected-(U23-Pad21)") (class "Default")
      (node (ref "U23") (pin "21") (pinfunction "21_21") (pintype "passive+no_connect"))
    )
    (net (code "108") (name "unconnected-(U23-Pad22)") (class "Default")
      (node (ref "U23") (pin "22") (pinfunction "22_22") (pintype "passive+no_connect"))
    )
    (net (code "109") (name "unconnected-(U23-Pad23)") (class "Default")
      (node (ref "U23") (pin "23") (pinfunction "23_23") (pintype "passive+no_connect"))
    )
    (net (code "110") (name "unconnected-(U23-Pad24)") (class "Default")
      (node (ref "U23") (pin "24") (pinfunction "24_24") (pintype "passive+no_connect"))
    )
    (net (code "111") (name "unconnected-(U23-Pad27)") (class "Default")
      (node (ref "U23") (pin "27") (pinfunction "27_27") (pintype "passive+no_connect"))
    )
    (net (code "112") (name "unconnected-(U23-Pad28)") (class "Default")
      (node (ref "U23") (pin "28") (pinfunction "28_28") (pintype "passive+no_connect"))
    )
    (net (code "113") (name "unconnected-(U23-Pad29)") (class "Default")
      (node (ref "U23") (pin "29") (pinfunction "29_29") (pintype "passive+no_connect"))
    )
    (net (code "114") (name "unconnected-(U23-Pad30)") (class "Default")
      (node (ref "U23") (pin "30") (pinfunction "30_30") (pintype "passive+no_connect"))
    )
    (net (code "115") (name "unconnected-(U23-Pad33)") (class "Default")
      (node (ref "U23") (pin "33") (pinfunction "33_33") (pintype "passive+no_connect"))
    )
    (net (code "116") (name "unconnected-(U23-Pad34)") (class "Default")
      (node (ref "U23") (pin "34") (pinfunction "34_34") (pintype "passive+no_connect"))
    )
    (net (code "117") (name "unconnected-(U23-Pad35)") (class "Default")
      (node (ref "U23") (pin "35") (pinfunction "35_35") (pintype "passive+no_connect"))
    )
    (net (code "118") (name "unconnected-(U23-Pad36)") (class "Default")
      (node (ref "U23") (pin "36") (pinfunction "36_36") (pintype "passive+no_connect"))
    )
    (net (code "119") (name "unconnected-(U23-Pad39)") (class "Default")
      (node (ref "U23") (pin "39") (pinfunction "39_39") (pintype "passive+no_connect"))
    )
    (net (code "120") (name "unconnected-(U23-Pad40)") (class "Default")
      (node (ref "U23") (pin "40") (pinfunction "40_40") (pintype "passive+no_connect"))
    )
    (net (code "121") (name "unconnected-(U23-Pad41)") (class "Default")
      (node (ref "U23") (pin "41") (pinfunction "41_41") (pintype "passive+no_connect"))
    )
    (net (code "122") (name "unconnected-(U23-Pad42)") (class "Default")
      (node (ref "U23") (pin "42") (pinfunction "42_42") (pintype "passive+no_connect"))
    )
    (net (code "123") (name "unconnected-(U23-Pad43)") (class "Default")
      (node (ref "U23") (pin "43") (pinfunction "43_43") (pintype "passive+no_connect"))
    )
    (net (code "124") (name "unconnected-(U23-Pad45)") (class "Default")
      (node (ref "U23") (pin "45") (pinfunction "45_45") (pintype "passive+no_connect"))
    )
    (net (code "125") (name "unconnected-(U23-Pad46)") (class "Default")
      (node (ref "U23") (pin "46") (pinfunction "46_46") (pintype "passive+no_connect"))
    )
    (net (code "126") (name "unconnected-(U23-Pad47)") (class "Default")
      (node (ref "U23") (pin "47") (pinfunction "47_47") (pintype "passive+no_connect"))
    )
    (net (code "127") (name "unconnected-(U23-Pad48)") (class "Default")
      (node (ref "U23") (pin "48") (pinfunction "48_48") (pintype "passive+no_connect"))
    )
    (net (code "128") (name "unconnected-(U23-Pad49)") (class "Default")
      (node (ref "U23") (pin "49") (pinfunction "49_49") (pintype "passive+no_connect"))
    )
    (net (code "129") (name "unconnected-(U23-Pad51)") (class "Default")
      (node (ref "U23") (pin "51") (pinfunction "51_51") (pintype "passive+no_connect"))
    )
    (net (code "130") (name "unconnected-(U23-Pad52)") (class "Default")
      (node (ref "U23") (pin "52") (pinfunction "52_52") (pintype "passive+no_connect"))
    )
    (net (code "131") (name "unconnected-(U23-Pad53)") (class "Default")
      (node (ref "U23") (pin "53") (pinfunction "53_53") (pintype "passive+no_connect"))
    )
    (net (code "132") (name "unconnected-(U23-Pad54)") (class "Default")
      (node (ref "U23") (pin "54") (pinfunction "54_54") (pintype "passive+no_connect"))
    )
    (net (code "133") (name "unconnected-(U23-Pad57)") (class "Default")
      (node (ref "U23") (pin "57") (pinfunction "57_57") (pintype "passive+no_connect"))
    )
    (net (code "134") (name "unconnected-(U23-Pad58)") (class "Default")
      (node (ref "U23") (pin "58") (pinfunction "58_58") (pintype "passive+no_connect"))
    )
    (net (code "135") (name "unconnected-(U23-Pad59)") (class "Default")
      (node (ref "U23") (pin "59") (pinfunction "59_59") (pintype "passive+no_connect"))
    )
    (net (code "136") (name "unconnected-(U23-Pad60)") (class "Default")
      (node (ref "U23") (pin "60") (pinfunction "60_60") (pintype "passive+no_connect"))
    )
    (net (code "137") (name "unconnected-(U23-Pad63)") (class "Default")
      (node (ref "U23") (pin "63") (pinfunction "63_63") (pintype "passive+no_connect"))
    )
    (net (code "138") (name "unconnected-(U23-Pad64)") (class "Default")
      (node (ref "U23") (pin "64") (pinfunction "64_64") (pintype "passive+no_connect"))
    )
    (net (code "139") (name "unconnected-(U23-Pad65)") (class "Default")
      (node (ref "U23") (pin "65") (pinfunction "65_65") (pintype "passive+no_connect"))
    )
    (net (code "140") (name "unconnected-(U23-Pad66)") (class "Default")
      (node (ref "U23") (pin "66") (pinfunction "66_66") (pintype "passive+no_connect"))
    )
    (net (code "141") (name "unconnected-(U23-Pad69)") (class "Default")
      (node (ref "U23") (pin "69") (pinfunction "69_69") (pintype "passive+no_connect"))
    )
    (net (code "142") (name "unconnected-(U23-Pad70)") (class "Default")
      (node (ref "U23") (pin "70") (pinfunction "70_70") (pintype "passive+no_connect"))
    )
    (net (code "143") (name "unconnected-(U23-Pad71)") (class "Default")
      (node (ref "U23") (pin "71") (pinfunction "71_71") (pintype "passive+no_connect"))
    )
    (net (code "144") (name "unconnected-(U23-Pad72)") (class "Default")
      (node (ref "U23") (pin "72") (pinfunction "72_72") (pintype "passive+no_connect"))
    )
    (net (code "145") (name "unconnected-(U23-Pad75)") (class "Default")
      (node (ref "U23") (pin "75") (pinfunction "75_75") (pintype "passive+no_connect"))
    )
    (net (code "146") (name "unconnected-(U23-Pad76)") (class "Default")
      (node (ref "U23") (pin "76") (pinfunction "76_76") (pintype "passive+no_connect"))
    )
    (net (code "147") (name "unconnected-(U23-Pad77)") (class "Default")
      (node (ref "U23") (pin "77") (pinfunction "77_77") (pintype "passive+no_connect"))
    )
    (net (code "148") (name "unconnected-(U23-Pad78)") (class "Default")
      (node (ref "U23") (pin "78") (pinfunction "78_78") (pintype "passive+no_connect"))
    )
    (net (code "149") (name "unconnected-(U23-Pad81)") (class "Default")
      (node (ref "U23") (pin "81") (pinfunction "81_81") (pintype "passive+no_connect"))
    )
    (net (code "150") (name "unconnected-(U23-Pad82)") (class "Default")
      (node (ref "U23") (pin "82") (pinfunction "82_82") (pintype "passive+no_connect"))
    )
    (net (code "151") (name "unconnected-(U23-Pad83)") (class "Default")
      (node (ref "U23") (pin "83") (pinfunction "83_83") (pintype "passive+no_connect"))
    )
    (net (code "152") (name "unconnected-(U23-Pad84)") (class "Default")
      (node (ref "U23") (pin "84") (pinfunction "84_84") (pintype "passive+no_connect"))
    )
    (net (code "153") (name "unconnected-(U23-Pad87)") (class "Default")
      (node (ref "U23") (pin "87") (pinfunction "87_87") (pintype "passive+no_connect"))
    )
    (net (code "154") (name "unconnected-(U23-Pad88)") (class "Default")
      (node (ref "U23") (pin "88") (pinfunction "88_88") (pintype "passive+no_connect"))
    )
    (net (code "155") (name "unconnected-(U23-Pad89)") (class "Default")
      (node (ref "U23") (pin "89") (pinfunction "89_89") (pintype "passive+no_connect"))
    )
    (net (code "156") (name "unconnected-(U23-Pad90)") (class "Default")
      (node (ref "U23") (pin "90") (pinfunction "90_90") (pintype "passive+no_connect"))
    )
    (net (code "157") (name "unconnected-(U23-Pad93)") (class "Default")
      (node (ref "U23") (pin "93") (pinfunction "93_93") (pintype "passive+no_connect"))
    )
    (net (code "158") (name "unconnected-(U23-Pad94)") (class "Default")
      (node (ref "U23") (pin "94") (pinfunction "94_94") (pintype "passive+no_connect"))
    )
    (net (code "159") (name "unconnected-(U23-Pad95)") (class "Default")
      (node (ref "U23") (pin "95") (pinfunction "95_95") (pintype "passive+no_connect"))
    )
    (net (code "160") (name "unconnected-(U23-Pad96)") (class "Default")
      (node (ref "U23") (pin "96") (pinfunction "96_96") (pintype "passive+no_connect"))
    )
    (net (code "161") (name "unconnected-(U23-Pad99)") (class "Default")
      (node (ref "U23") (pin "99") (pinfunction "99_99") (pintype "passive+no_connect"))
    )
    (net (code "162") (name "unconnected-(U23-Pad100)") (class "Default")
      (node (ref "U23") (pin "100") (pinfunction "100_100") (pintype "passive+no_connect"))
    )
  )
)
